# MISC.net
KiCad netlist of a schematic drawn in Altium Designer
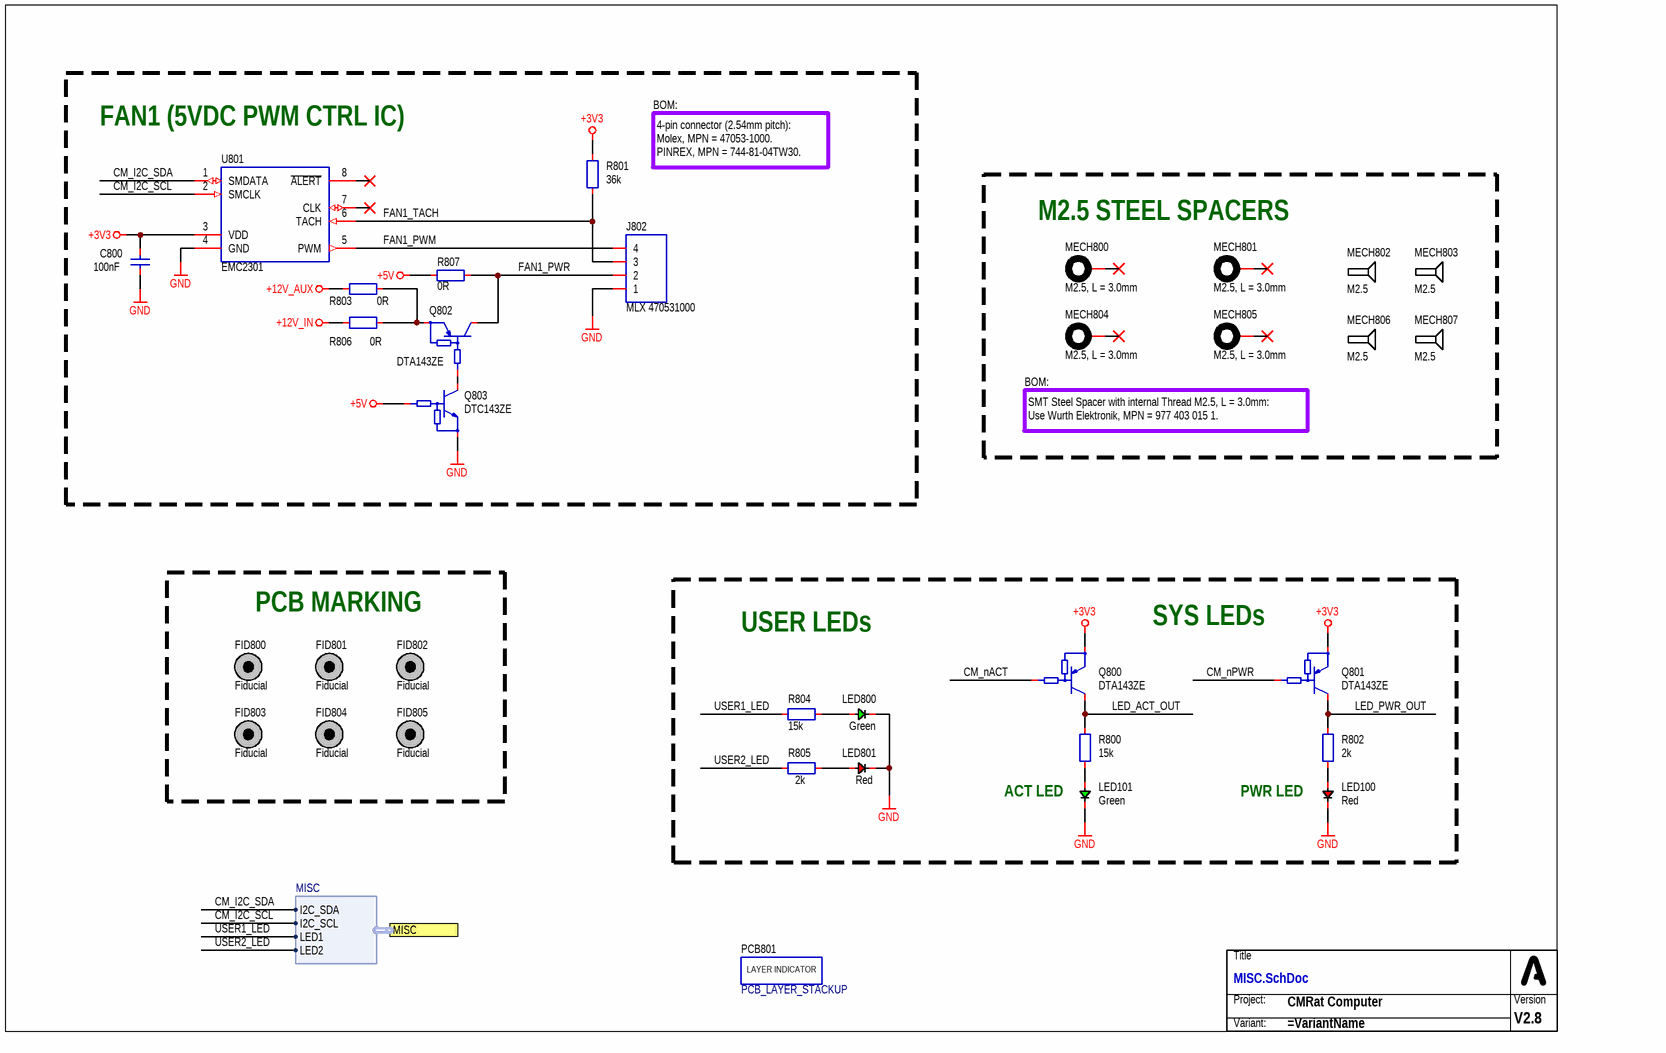
[diagram p0: MISC.SchDoc]

(export (version "E")
  (design (tool "Eeschema 10.0.6"))
  (components
    (comp (ref "C800")
      (value "100nF")
      (footprint "CAP_0603_R")
      (description "Capacitor; MLCC; 100nF; 10V X5R")
      (fields (field (name "MANUFACTURER") "YAGEO") (field (name "MPN") "CC0603KRX7R9BB104"))
      (libsource (lib "MirFol_db_local") (part "CAP"))
    )
    (comp (ref "FID800")
      (value "Fiducial")
      (footprint "PCB_FID_RND_100x300")
      (description "PCB Marking; Fiducial; Round;")
      (libsource (lib "MirFol_lib") (part "PCB_FID_RND"))
    )
    (comp (ref "FID801")
      (value "Fiducial")
      (footprint "PCB_FID_RND_100x300")
      (description "PCB Marking; Fiducial; Round;")
      (libsource (lib "MirFol_lib") (part "PCB_FID_RND"))
    )
    (comp (ref "FID802")
      (value "Fiducial")
      (footprint "PCB_FID_RND_100x300")
      (description "PCB Marking; Fiducial; Round;")
      (libsource (lib "MirFol_lib") (part "PCB_FID_RND"))
    )
    (comp (ref "FID803")
      (value "Fiducial")
      (footprint "PCB_FID_RND_100x300")
      (description "PCB Marking; Fiducial; Round;")
      (libsource (lib "MirFol_lib") (part "PCB_FID_RND"))
    )
    (comp (ref "FID804")
      (value "Fiducial")
      (footprint "PCB_FID_RND_100x300")
      (description "PCB Marking; Fiducial; Round;")
      (libsource (lib "MirFol_lib") (part "PCB_FID_RND"))
    )
    (comp (ref "FID805")
      (value "Fiducial")
      (footprint "PCB_FID_RND_100x300")
      (description "PCB Marking; Fiducial; Round;")
      (libsource (lib "MirFol_lib") (part "PCB_FID_RND"))
    )
    (comp (ref "J802")
      (value "MLX 470531000")
      (footprint "CON_MLX_470531000")
      (description "Connector; 1 Row; 470531000")
      (fields (field (name "MANUFACTURER") "Molex") (field (name "MPN") "470531000"))
      (libsource (lib "MirFol_lib") (part "CON_1X04_COL"))
    )
    (comp (ref "LED100")
      (value "Red")
      (footprint "LED_0805_RED_R")
      (description "Diode; LED; Red;")
      (fields
        (field (name "MANUFACTURER") "Foshan NationStar Optoelectronics")
        (field (name "MPN") "NCD0805R1")
      )
      (libsource (lib "MirFol_lib") (part "DIO_LED_RED"))
    )
    (comp (ref "LED101")
      (value "Green")
      (footprint "LED_0805_GRN_R")
      (description "Diode; LED; Green;")
      (fields
        (field (name "MANUFACTURER") "Foshan NationStar Optoelectronics")
        (field (name "MPN") "NCD0805G1")
      )
      (libsource (lib "MirFol_lib") (part "DIO_LED_GRN"))
    )
    (comp (ref "LED800")
      (value "Green")
      (footprint "LED_0805_GRN_R")
      (description "Diode; LED; Green;")
      (fields
        (field (name "MANUFACTURER") "Foshan NationStar Optoelectronics")
        (field (name "MPN") "NCD0805G1")
      )
      (libsource (lib "MirFol_lib") (part "DIO_LED_GRN"))
    )
    (comp (ref "LED801")
      (value "Red")
      (footprint "LED_0805_RED_R")
      (description "Diode; LED; Red;")
      (fields
        (field (name "MANUFACTURER") "Foshan NationStar Optoelectronics")
        (field (name "MPN") "NCD0805R1")
      )
      (libsource (lib "MirFol_lib") (part "DIO_LED_RED"))
    )
    (comp (ref "MECH800")
      (value "M2.5, L = 3.0mm")
      (footprint "PCB_WRT_9774030151")
      (description "PCB; Mechanical; SMT Steel Spacer; M2.5;")
      (fields (field (name "MANUFACTURER") "Wurth Elektronik") (field (name "MPN") "977 403 015 1"))
      (libsource (lib "MirFol_lib") (part "PCB_MECH_WRT_WA-SMSI"))
    )
    (comp (ref "MECH801")
      (value "M2.5, L = 3.0mm")
      (footprint "PCB_WRT_9774030151")
      (description "PCB; Mechanical; SMT Steel Spacer; M2.5;")
      (fields (field (name "MANUFACTURER") "Wurth Elektronik") (field (name "MPN") "977 403 015 1"))
      (libsource (lib "MirFol_lib") (part "PCB_MECH_WRT_WA-SMSI"))
    )
    (comp (ref "MECH802")
      (value "M2.5")
      (description "Mechnical; Screw;")
      (fields (field (name "MPN") "M2.5 screw"))
      (libsource (lib "MirFol_lib") (part "PCB_MECH_SCR"))
    )
    (comp (ref "MECH803")
      (value "M2.5")
      (description "Mechnical; Screw;")
      (fields (field (name "MPN") "M2.5 screw"))
      (libsource (lib "MirFol_lib") (part "PCB_MECH_SCR"))
    )
    (comp (ref "MECH804")
      (value "M2.5, L = 3.0mm")
      (footprint "PCB_WRT_9774030151")
      (description "PCB; Mechanical; SMT Steel Spacer; M2.5;")
      (fields (field (name "MANUFACTURER") "Wurth Elektronik") (field (name "MPN") "977 403 015 1"))
      (libsource (lib "MirFol_lib") (part "PCB_MECH_WRT_WA-SMSI"))
    )
    (comp (ref "MECH805")
      (value "M2.5, L = 3.0mm")
      (footprint "PCB_WRT_9774030151")
      (description "PCB; Mechanical; SMT Steel Spacer; M2.5;")
      (fields (field (name "MANUFACTURER") "Wurth Elektronik") (field (name "MPN") "977 403 015 1"))
      (libsource (lib "MirFol_lib") (part "PCB_MECH_WRT_WA-SMSI"))
    )
    (comp (ref "MECH806")
      (value "M2.5")
      (description "Mechnical; Screw;")
      (fields (field (name "MPN") "M2.5 screw"))
      (libsource (lib "MirFol_lib") (part "PCB_MECH_SCR"))
    )
    (comp (ref "MECH807")
      (value "M2.5")
      (description "Mechnical; Screw;")
      (fields (field (name "MPN") "M2.5 screw"))
      (libsource (lib "MirFol_lib") (part "PCB_MECH_SCR"))
    )
    (comp (ref "PCB801")
      (value "PCB_LAYER_STACKUP")
      (footprint "PCB_STACKUP-4L_A2")
      (libsource (lib "MirFol_lib") (part "PCB_LAYER_STACKUP"))
    )
    (comp (ref "Q800")
      (value "DTA143ZE")
      (footprint "PKG_SOT523_SC75_SOT416_P100_R")
      (description "Transistor; BJT; PNP; Digital;")
      (fields (field (name "MANUFACTURER") "On Semiconductor"))
      (libsource (lib "AN_lib") (part "TRA_BJT_PNP_DIG_ONS_DTA143ZE"))
    )
    (comp (ref "Q801")
      (value "DTA143ZE")
      (footprint "PKG_SOT523_SC75_SOT416_P100_R")
      (description "Transistor; BJT; PNP; Digital;")
      (fields (field (name "MANUFACTURER") "On Semiconductor"))
      (libsource (lib "AN_lib") (part "TRA_BJT_PNP_DIG_ONS_DTA143ZE"))
    )
    (comp (ref "Q802")
      (value "DTA143ZE")
      (footprint "PKG_SOT523_SC75_SOT416_P100_R")
      (description "Transistor; BJT; PNP; Digital;")
      (fields (field (name "MANUFACTURER") "On Semiconductor"))
      (libsource (lib "AN_lib") (part "TRA_BJT_PNP_DIG_ONS_DTA143ZE"))
    )
    (comp (ref "Q803")
      (value "DTC143ZE")
      (footprint "PKG_SOT523_SC75_SOT416_P100_R")
      (description "Transistor; BJT; NPN; Digital;")
      (fields (field (name "MANUFACTURER") "On Semiconductor"))
      (libsource (lib "MirFol_lib") (part "TRA_BJT_NPN_DIG_BEC"))
    )
    (comp (ref "R800")
      (value "15k")
      (footprint "RES_0603_R")
      (description "Resistor; Thick Film; 15k; 1%; 100mW; 100PPM; 75V; Standard; SMD; 0603 (1608);")
      (fields (field (name "MANUFACTURER") "UNI-ROYAL(Uniroyal Elec)") (field (name "MPN") "0603WAF1502T5E"))
      (libsource (lib "MirFol_db_local") (part "RES"))
    )
    (comp (ref "R801")
      (value "36k")
      (footprint "RES_0603_R")
      (description "Resistor; Thick Film; 36k; SMD; 0603 (1608);")
      (fields (field (name "MANUFACTURER") "UNI-ROYAL(Uniroyal Elec)") (field (name "MPN") "0603WAF3602T5E"))
      (libsource (lib "MirFol_db_local") (part "RES"))
    )
    (comp (ref "R802")
      (value "2k")
      (footprint "RES_0603_R")
      (description "Resistor; Thick Film; 2k2; 1%; 100mW; 100PPM; 75V; Standard; SMD; 0603 (1608);")
      (fields (field (name "MANUFACTURER") "UNI-ROYAL(Uniroyal Elec)") (field (name "MPN") "0603WAF2001T5E"))
      (libsource (lib "MirFol_db_local") (part "RES"))
    )
    (comp (ref "R803")
      (value "0R")
      (footprint "RES_0603_R")
      (description "Resistor; Thick Film; 0R; SMD; 0603 (1608);")
      (fields (field (name "MANUFACTURER") "UNI-ROYAL(Uniroyal Elec)") (field (name "MPN") "0603WAF0000T5E"))
      (libsource (lib "") (part "RES_2"))
    )
    (comp (ref "R804")
      (value "15k")
      (footprint "RES_0603_R")
      (description "Resistor; Thick Film; 15k; 1%; 100mW; 100PPM; 75V; Standard; SMD; 0603 (1608);")
      (fields (field (name "MANUFACTURER") "UNI-ROYAL(Uniroyal Elec)") (field (name "MPN") "0603WAF1502T5E"))
      (libsource (lib "") (part "RES_1"))
    )
    (comp (ref "R805")
      (value "2k")
      (footprint "RES_0603_R")
      (description "Resistor; Thick Film; 2k2; 1%; 100mW; 100PPM; 75V; Standard; SMD; 0603 (1608);")
      (fields (field (name "MANUFACTURER") "UNI-ROYAL(Uniroyal Elec)") (field (name "MPN") "0603WAF2001T5E"))
      (libsource (lib "") (part "RES_1"))
    )
    (comp (ref "R806")
      (value "0R")
      (footprint "RES_0603_R")
      (description "Resistor; Thick Film; 0R; SMD; 0603 (1608);")
      (fields (field (name "MANUFACTURER") "UNI-ROYAL(Uniroyal Elec)") (field (name "MPN") "0603WAF0000T5E"))
      (libsource (lib "") (part "RES_2"))
    )
    (comp (ref "R807")
      (value "0R")
      (footprint "RES_0603_R")
      (description "Resistor; Thick Film; 0R; SMD; 0603 (1608);")
      (fields (field (name "MANUFACTURER") "UNI-ROYAL(Uniroyal Elec)") (field (name "MPN") "0603WAF0000T5E"))
      (libsource (lib "") (part "RES_2"))
    )
    (comp (ref "TB800") (value "~") (libsource (lib "Symbols_NO_BOM") (part "SCH_TITLE_BLOCK_SIMPLE_NODATE")))
    (comp (ref "U801")
      (value "EMC2301")
      (footprint "ICC_TSSOP8_300X300X110P65")
      (description "IC; Fan controller;")
      (fields (field (name "MANUFACTURER") "Microchip Technology") (field (name "MPN") "EMC2301-1-ACZL-TR"))
      (libsource (lib "MirFol_lib") (part "ICC_MCP_EMC2301_MSOP-8"))
    )
  )
  (nets
    (net (code "2") (name "+3V3") (class "Default")
      (node (ref "C800") (pin "2") (pintype "passive"))
      (node (ref "Q800") (pin "2") (pinfunction "E_2") (pintype "passive"))
      (node (ref "Q801") (pin "2") (pinfunction "E_2") (pintype "passive"))
      (node (ref "R801") (pin "2") (pinfunction "2_2") (pintype "passive"))
      (node (ref "U801") (pin "3") (pinfunction "VDD_3") (pintype "power_in"))
    )
    (net (code "3") (name "+5V") (class "Default")
      (node (ref "Q803") (pin "1") (pinfunction "B_1") (pintype "passive"))
      (node (ref "R807") (pin "2") (pinfunction "2_2") (pintype "passive"))
    )
    (net (code "4") (name "+12V_AUX") (class "Default")
      (node (ref "R803") (pin "2") (pinfunction "2_2") (pintype "passive"))
    )
    (net (code "5") (name "+12V_IN") (class "Default")
      (node (ref "R806") (pin "2") (pinfunction "2_2") (pintype "passive"))
    )
    (net (code "6") (name "/CM_I2C_SCL") (class "Default")
      (node (ref "U801") (pin "2") (pinfunction "SMCLK_2") (pintype "input"))
    )
    (net (code "7") (name "/CM_I2C_SDA") (class "Default")
      (node (ref "U801") (pin "1") (pinfunction "SMDATA_1") (pintype "bidirectional"))
    )
    (net (code "8") (name "/CM_nACT") (class "Default")
      (node (ref "Q800") (pin "1") (pinfunction "B_1") (pintype "passive"))
    )
    (net (code "9") (name "/CM_nPWR") (class "Default")
      (node (ref "Q801") (pin "1") (pinfunction "B_1") (pintype "passive"))
    )
    (net (code "10") (name "/FAN1_PWM") (class "Default")
      (node (ref "J802") (pin "4") (pinfunction "4_4") (pintype "passive"))
      (node (ref "U801") (pin "5") (pinfunction "PWM_5") (pintype "output"))
    )
    (net (code "11") (name "/FAN1_PWR") (class "Default")
      (node (ref "J802") (pin "2") (pinfunction "2_2") (pintype "passive"))
      (node (ref "Q802") (pin "3") (pinfunction "C_3") (pintype "passive"))
      (node (ref "R807") (pin "1") (pinfunction "1_1") (pintype "passive"))
    )
    (net (code "12") (name "/FAN1_TACH") (class "Default")
      (node (ref "J802") (pin "3") (pinfunction "3_3") (pintype "passive"))
      (node (ref "R801") (pin "1") (pinfunction "1_1") (pintype "passive"))
      (node (ref "U801") (pin "6") (pinfunction "TACH_6") (pintype "input"))
    )
    (net (code "13") (name "/LED_ACT_OUT") (class "Default")
      (node (ref "Q800") (pin "3") (pinfunction "C_3") (pintype "passive"))
      (node (ref "R800") (pin "2") (pinfunction "2_2") (pintype "passive"))
    )
    (net (code "14") (name "/LED_PWR_OUT") (class "Default")
      (node (ref "Q801") (pin "3") (pinfunction "C_3") (pintype "passive"))
      (node (ref "R802") (pin "2") (pinfunction "2_2") (pintype "passive"))
    )
    (net (code "15") (name "/USER1_LED") (class "Default")
      (node (ref "R804") (pin "1") (pinfunction "1_1") (pintype "passive"))
    )
    (net (code "16") (name "/USER2_LED") (class "Default")
      (node (ref "R805") (pin "1") (pinfunction "1_1") (pintype "passive"))
    )
    (net (code "18") (name "GND") (class "Default")
      (node (ref "C800") (pin "1") (pintype "passive"))
      (node (ref "J802") (pin "1") (pinfunction "1_1") (pintype "passive"))
      (node (ref "LED100") (pin "1") (pinfunction "1_1") (pintype "passive"))
      (node (ref "LED101") (pin "1") (pinfunction "1_1") (pintype "passive"))
      (node (ref "LED800") (pin "1") (pinfunction "1_1") (pintype "passive"))
      (node (ref "LED801") (pin "1") (pinfunction "1_1") (pintype "passive"))
      (node (ref "Q803") (pin "2") (pinfunction "E_2") (pintype "passive"))
      (node (ref "U801") (pin "4") (pinfunction "GND_4") (pintype "power_in"))
    )
    (net (code "19") (name "Net-(LED100-Pad2)") (class "Default")
      (node (ref "LED100") (pin "2") (pinfunction "2_2") (pintype "passive"))
      (node (ref "R802") (pin "1") (pinfunction "1_1") (pintype "passive"))
    )
    (net (code "20") (name "Net-(LED101-Pad2)") (class "Default")
      (node (ref "LED101") (pin "2") (pinfunction "2_2") (pintype "passive"))
      (node (ref "R800") (pin "1") (pinfunction "1_1") (pintype "passive"))
    )
    (net (code "21") (name "Net-(LED800-Pad2)") (class "Default")
      (node (ref "LED800") (pin "2") (pinfunction "2_2") (pintype "passive"))
      (node (ref "R804") (pin "2") (pinfunction "2_2") (pintype "passive"))
    )
    (net (code "22") (name "Net-(LED801-Pad2)") (class "Default")
      (node (ref "LED801") (pin "2") (pinfunction "2_2") (pintype "passive"))
      (node (ref "R805") (pin "2") (pinfunction "2_2") (pintype "passive"))
    )
    (net (code "23") (name "Net-(Q802-B)") (class "Default")
      (node (ref "Q802") (pin "1") (pinfunction "B_1") (pintype "passive"))
      (node (ref "Q803") (pin "3") (pinfunction "C_3") (pintype "passive"))
    )
    (net (code "24") (name "Net-(Q802-E)") (class "Default")
      (node (ref "Q802") (pin "2") (pinfunction "E_2") (pintype "passive"))
      (node (ref "R803") (pin "1") (pinfunction "1_1") (pintype "passive"))
      (node (ref "R806") (pin "1") (pinfunction "1_1") (pintype "passive"))
    )
    (net (code "25") (name "unconnected-(MECH800-Pad1)") (class "Default")
      (node (ref "MECH800") (pin "1") (pinfunction "1_1") (pintype "passive+no_connect"))
    )
    (net (code "26") (name "unconnected-(MECH801-Pad1)") (class "Default")
      (node (ref "MECH801") (pin "1") (pinfunction "1_1") (pintype "passive+no_connect"))
    )
    (net (code "27") (name "unconnected-(MECH804-Pad1)") (class "Default")
      (node (ref "MECH804") (pin "1") (pinfunction "1_1") (pintype "passive+no_connect"))
    )
    (net (code "28") (name "unconnected-(MECH805-Pad1)") (class "Default")
      (node (ref "MECH805") (pin "1") (pinfunction "1_1") (pintype "passive+no_connect"))
    )
    (net (code "29") (name "unconnected-(U801-CLK-Pad7)") (class "Default")
      (node (ref "U801") (pin "7") (pinfunction "CLK_7") (pintype "bidirectional+no_connect"))
    )
    (net (code "30") (name "unconnected-(U801-~{ALERT}-Pad8)") (class "Default")
      (node (ref "U801") (pin "8") (pinfunction "~{ALERT}_8") (pintype "open_collector+no_connect"))
    )
  )
)
